# DM2080_LEFT_OV9782.net
KiCad netlist of a schematic drawn in Altium Designer
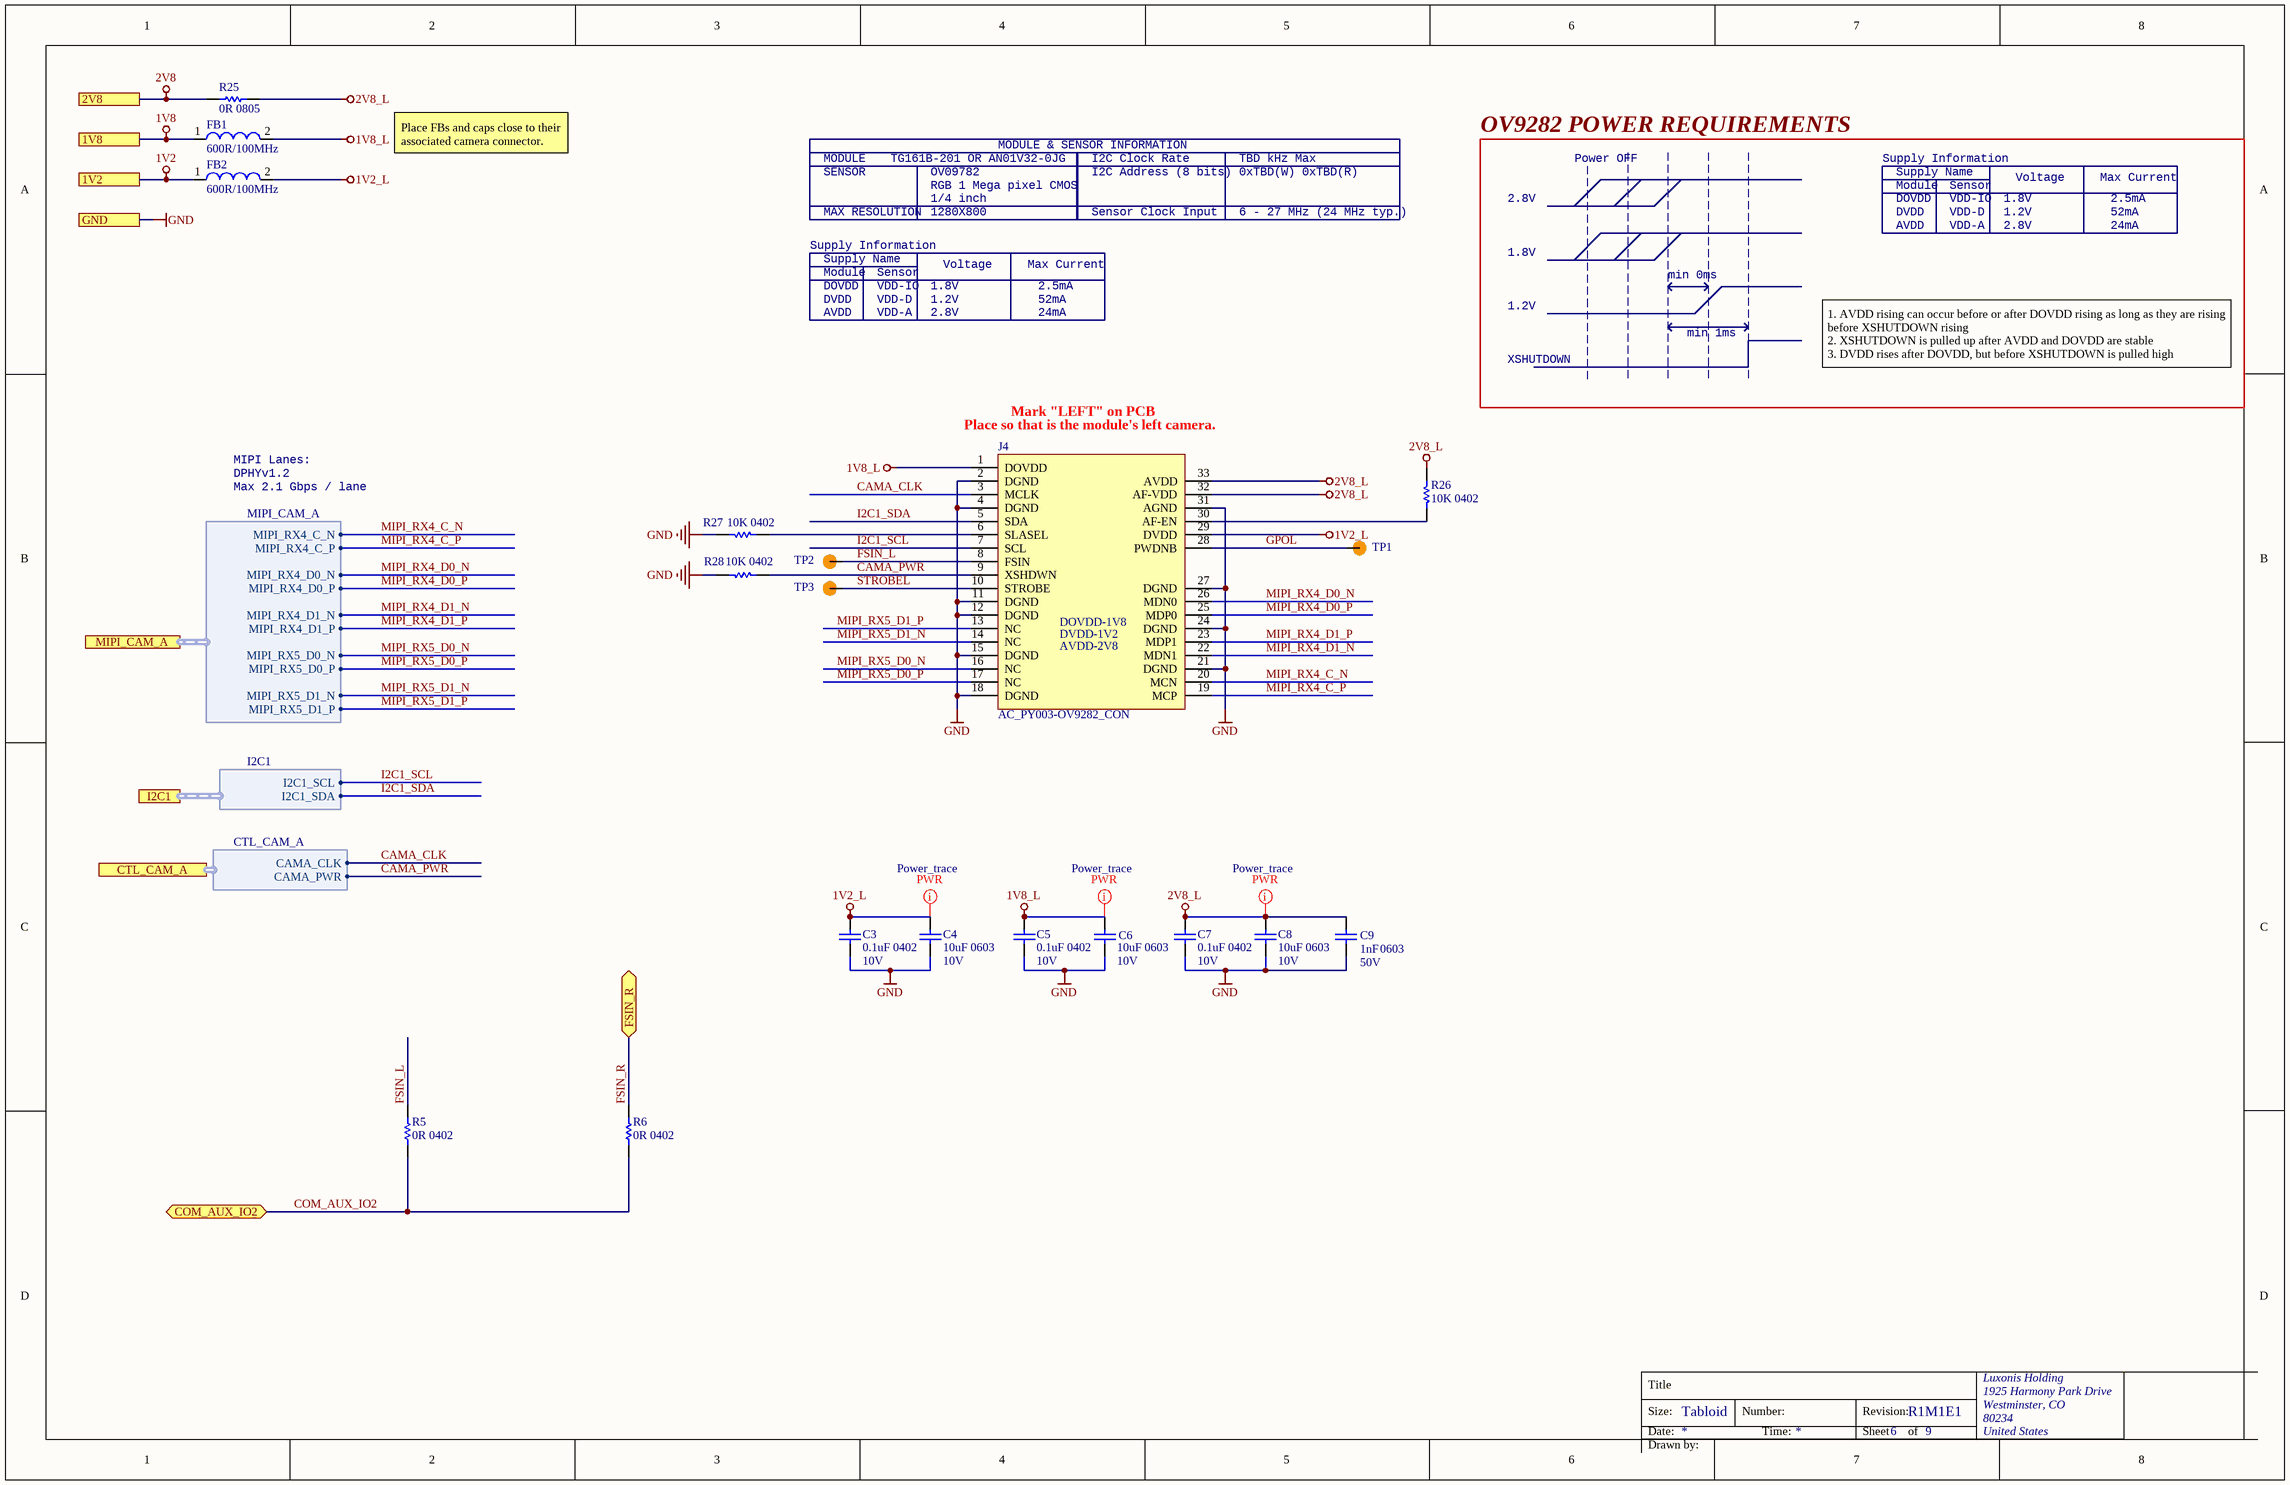
[diagram p0: DM2080_LEFT_OV9782.SchDoc]

(export (version "E")
  (design (tool "Eeschema 10.0.6"))
  (components
    (comp (ref "C3")
      (value "0.1uF 0402")
      (footprint "CAP_Altium_Vault_Generic:CAPC0402(1005)70_L")
      (description "CAP CER 0.1UF 10V X7R 0402 5%")
      (fields (field (name "TOLERANCE") "5%") (field (name "VOLTAGE RATING") "10V"))
      (libsource (lib "LuxonisMaster") (part "GRM155R71A104JA01D"))
    )
    (comp (ref "C4")
      (value "10uF 0603")
      (footprint "CAP_Altium_Vault_Generic:CAPC0603(1608)100_L")
      (description "CAP CER 10UF 10V X5R 0603 20%")
      (fields (field (name "TOLERANCE") "20%") (field (name "VOLTAGE RATING") "10V"))
      (libsource (lib "LuxonisMaster") (part "GRM188R61A106ME69D"))
    )
    (comp (ref "C5")
      (value "0.1uF 0402")
      (footprint "CAP_Altium_Vault_Generic:CAPC0402(1005)70_L")
      (description "CAP CER 0.1UF 10V X7R 0402 5%")
      (fields (field (name "TOLERANCE") "5%") (field (name "VOLTAGE RATING") "10V"))
      (libsource (lib "LuxonisMaster") (part "GRM155R71A104JA01D"))
    )
    (comp (ref "C6")
      (value "10uF 0603")
      (footprint "CAP_Altium_Vault_Generic:CAPC0603(1608)100_L")
      (description "CAP CER 10UF 10V X5R 0603 20%")
      (fields (field (name "TOLERANCE") "20%") (field (name "VOLTAGE RATING") "10V"))
      (libsource (lib "LuxonisMaster") (part "GRM188R61A106ME69D"))
    )
    (comp (ref "C7")
      (value "0.1uF 0402")
      (footprint "CAP_Altium_Vault_Generic:CAPC0402(1005)70_L")
      (description "CAP CER 0.1UF 10V X7R 0402 5%")
      (fields (field (name "TOLERANCE") "5%") (field (name "VOLTAGE RATING") "10V"))
      (libsource (lib "LuxonisMaster") (part "GRM155R71A104JA01D"))
    )
    (comp (ref "C8")
      (value "10uF 0603")
      (footprint "CAP_Altium_Vault_Generic:CAPC0603(1608)100_L")
      (description "CAP CER 10UF 10V X5R 0603 20%")
      (fields (field (name "TOLERANCE") "20%") (field (name "VOLTAGE RATING") "10V"))
      (libsource (lib "LuxonisMaster") (part "GRM188R61A106ME69D"))
    )
    (comp (ref "C9")
      (value "1nF 0603 C0G")
      (footprint "CAP_Altium_Vault_Generic:CAPC0603(1608)100_L")
      (description "CAP CER 1000PF 50V C0G/NP0 0603")
      (fields
        (field (name "MANUFACTURER") "Murata")
        (field (name "MANUFACTURER PART NUMBER") "GRM1885C1H102FA01D")
        (field (name "CASE/PACKAGE") "0603")
        (field (name "CAPACITANCE") "1nF")
        (field (name "VOLTAGE RATING") "50V")
      )
      (libsource (lib "LuxonisMaster") (part "GRM1885C1H102FA01D"))
    )
    (comp (ref "FB1")
      (value "600R/100MHz")
      (footprint "LuxonisMaster:2508056017Y2")
      (description "FERRITE BEAD, 0.1OHM, 2A, 0805, 600R/100MHz")
      (fields (field (name "TOLERANCE") "25%"))
      (libsource (lib "LuxonisMaster") (part "2508056017Y2"))
    )
    (comp (ref "FB2")
      (value "600R/100MHz")
      (footprint "LuxonisMaster:2508056017Y2")
      (description "FERRITE BEAD, 0.1OHM, 2A, 0805, 600R/100MHz")
      (fields (field (name "TOLERANCE") "25%"))
      (libsource (lib "LuxonisMaster") (part "2508056017Y2"))
    )
    (comp (ref "J4")
      (value "AC_PY003-OV9282_CON")
      (footprint "AC-PY003-OV9282")
      (description "FFC/FPC Connector, 33 Contact(s), 1 Row(s), Female, Right Angle, Surface Mount Terminal")
      (libsource (lib "Luxonis LLC") (part "AC_PY003-OV9282_CON"))
    )
    (comp (ref "R5")
      (value "0R 0402")
      (footprint "RES_Altium_Vault_Generic:RESC0402(1005)_L")
      (description "RES SMD 0 OHM JUMPER 1/16W 0402")
      (fields (field (name "TOLERANCE") "5%"))
      (libsource (lib "LuxonisMaster") (part "CRCW04020000Z0ED"))
    )
    (comp (ref "R6")
      (value "0R 0402")
      (footprint "RES_Altium_Vault_Generic:RESC0402(1005)_L")
      (description "RES SMD 0 OHM JUMPER 1/16W 0402")
      (fields (field (name "TOLERANCE") "5%"))
      (libsource (lib "LuxonisMaster") (part "CRCW04020000Z0ED"))
    )
    (comp (ref "R25")
      (value "0R 0805")
      (footprint "RESC0805(2012)_L")
      (description "RES SMD 0.0R OHM 1% 1/8W 0805")
      (libsource (lib "LuxonisMaster") (part "CRCW08050000Z0EA"))
    )
    (comp (ref "R26")
      (value "10K 0402")
      (footprint "RES_Altium_Vault_Generic:RESC0402(1005)_L")
      (fields (field (name "TOLERANCE") "1%"))
      (libsource (lib "LuxonisMaster") (part "RC0402FR-1310KL"))
    )
    (comp (ref "R27")
      (value "10K 0402")
      (footprint "RES_Altium_Vault_Generic:RESC0402(1005)_L")
      (fields (field (name "TOLERANCE") "1%"))
      (libsource (lib "LuxonisMaster") (part "RC0402FR-1310KL"))
    )
    (comp (ref "R28")
      (value "10K 0402")
      (footprint "RES_Altium_Vault_Generic:RESC0402(1005)_L")
      (fields (field (name "TOLERANCE") "1%"))
      (libsource (lib "LuxonisMaster") (part "RC0402FR-1310KL"))
    )
    (comp (ref "TP1")
      (value "TP100_200_NS")
      (footprint "LuxonisMaster:TP100_200_NS")
      (libsource (lib "LuxonisMaster") (part "TEST_POINT"))
    )
    (comp (ref "TP2")
      (value "TP100_200_NS")
      (footprint "LuxonisMaster:TP100_200_NS")
      (libsource (lib "LuxonisMaster") (part "TEST_POINT"))
    )
    (comp (ref "TP3")
      (value "TP100_200_NS")
      (footprint "LuxonisMaster:TP100_200_NS")
      (libsource (lib "LuxonisMaster") (part "TEST_POINT"))
    )
  )
  (nets
    (net (code "4") (name "/CAMA_CLK") (class "Default")
      (node (ref "J4") (pin "3") (pinfunction "MCLK_3") (pintype "passive"))
    )
    (net (code "5") (name "/CAMA_PWR") (class "Default")
      (node (ref "J4") (pin "9") (pinfunction "XSHDWN_9") (pintype "passive"))
      (node (ref "R28") (pin "1") (pinfunction "1_1") (pintype "passive"))
    )
    (net (code "6") (name "/COM_AUX_IO2") (class "Default")
      (node (ref "R5") (pin "2") (pinfunction "2_2") (pintype "passive"))
      (node (ref "R6") (pin "2") (pinfunction "2_2") (pintype "passive"))
    )
    (net (code "7") (name "/FSIN_L") (class "Default")
      (node (ref "J4") (pin "8") (pinfunction "FSIN_8") (pintype "passive"))
      (node (ref "R5") (pin "1") (pinfunction "1_1") (pintype "passive"))
      (node (ref "TP2") (pin "1") (pintype "passive"))
    )
    (net (code "8") (name "/FSIN_R") (class "Default")
      (node (ref "R6") (pin "1") (pinfunction "1_1") (pintype "passive"))
    )
    (net (code "9") (name "/GPOL") (class "Default")
      (node (ref "J4") (pin "28") (pinfunction "PWDNB_28") (pintype "passive"))
      (node (ref "TP1") (pin "1") (pintype "passive"))
    )
    (net (code "10") (name "/I2C1_SCL") (class "Default")
      (node (ref "J4") (pin "7") (pinfunction "SCL_7") (pintype "passive"))
    )
    (net (code "11") (name "/I2C1_SDA") (class "Default")
      (node (ref "J4") (pin "5") (pinfunction "SDA_5") (pintype "passive"))
    )
    (net (code "12") (name "/MIPI_RX4_C_N") (class "Default")
      (node (ref "J4") (pin "20") (pinfunction "MCN_20") (pintype "passive"))
    )
    (net (code "13") (name "/MIPI_RX4_C_P") (class "Default")
      (node (ref "J4") (pin "19") (pinfunction "MCP_19") (pintype "passive"))
    )
    (net (code "14") (name "/MIPI_RX4_D0_N") (class "Default")
      (node (ref "J4") (pin "26") (pinfunction "MDN0_26") (pintype "passive"))
    )
    (net (code "15") (name "/MIPI_RX4_D0_P") (class "Default")
      (node (ref "J4") (pin "25") (pinfunction "MDP0_25") (pintype "passive"))
    )
    (net (code "16") (name "/MIPI_RX4_D1_N") (class "Default")
      (node (ref "J4") (pin "22") (pinfunction "MDN1_22") (pintype "passive"))
    )
    (net (code "17") (name "/MIPI_RX4_D1_P") (class "Default")
      (node (ref "J4") (pin "23") (pinfunction "MDP1_23") (pintype "passive"))
    )
    (net (code "18") (name "/MIPI_RX5_D0_N") (class "Default")
      (node (ref "J4") (pin "16") (pinfunction "NC_16") (pintype "passive"))
    )
    (net (code "19") (name "/MIPI_RX5_D0_P") (class "Default")
      (node (ref "J4") (pin "17") (pinfunction "NC_17") (pintype "passive"))
    )
    (net (code "20") (name "/MIPI_RX5_D1_N") (class "Default")
      (node (ref "J4") (pin "14") (pinfunction "NC_14") (pintype "passive"))
    )
    (net (code "21") (name "/MIPI_RX5_D1_P") (class "Default")
      (node (ref "J4") (pin "13") (pinfunction "NC_13") (pintype "passive"))
    )
    (net (code "22") (name "/STROBEL") (class "Default")
      (node (ref "J4") (pin "10") (pinfunction "STROBE_10") (pintype "passive"))
      (node (ref "TP3") (pin "1") (pintype "passive"))
    )
    (net (code "26") (name "1V2") (class "Default")
      (node (ref "FB2") (pin "1") (pinfunction "1_1") (pintype "passive"))
    )
    (net (code "27") (name "1V2_L") (class "Default")
      (node (ref "C3") (pin "2") (pinfunction "2_2") (pintype "passive"))
      (node (ref "C4") (pin "2") (pinfunction "2_2") (pintype "passive"))
      (node (ref "FB2") (pin "2") (pinfunction "2_2") (pintype "passive"))
      (node (ref "J4") (pin "29") (pinfunction "DVDD_29") (pintype "passive"))
    )
    (net (code "28") (name "1V8") (class "Default")
      (node (ref "FB1") (pin "1") (pinfunction "1_1") (pintype "passive"))
    )
    (net (code "29") (name "1V8_L") (class "Default")
      (node (ref "C5") (pin "2") (pinfunction "2_2") (pintype "passive"))
      (node (ref "C6") (pin "2") (pinfunction "2_2") (pintype "passive"))
      (node (ref "FB1") (pin "2") (pinfunction "2_2") (pintype "passive"))
      (node (ref "J4") (pin "1") (pinfunction "DOVDD_1") (pintype "passive"))
    )
    (net (code "30") (name "2V8") (class "Default")
      (node (ref "R25") (pin "1") (pinfunction "1_1") (pintype "passive"))
    )
    (net (code "31") (name "2V8_L") (class "Default")
      (node (ref "C7") (pin "2") (pinfunction "2_2") (pintype "passive"))
      (node (ref "C8") (pin "2") (pinfunction "2_2") (pintype "passive"))
      (node (ref "C9") (pin "2") (pinfunction "2_2") (pintype "passive"))
      (node (ref "J4") (pin "32") (pinfunction "AF-VDD_32") (pintype "passive"))
      (node (ref "J4") (pin "33") (pinfunction "AVDD_33") (pintype "passive"))
      (node (ref "R25") (pin "2") (pinfunction "2_2") (pintype "passive"))
      (node (ref "R26") (pin "1") (pinfunction "1_1") (pintype "passive"))
    )
    (net (code "32") (name "GND") (class "Default")
      (node (ref "C3") (pin "1") (pinfunction "1_1") (pintype "passive"))
      (node (ref "C4") (pin "1") (pinfunction "1_1") (pintype "passive"))
      (node (ref "C5") (pin "1") (pinfunction "1_1") (pintype "passive"))
      (node (ref "C6") (pin "1") (pinfunction "1_1") (pintype "passive"))
      (node (ref "C7") (pin "1") (pinfunction "1_1") (pintype "passive"))
      (node (ref "C8") (pin "1") (pinfunction "1_1") (pintype "passive"))
      (node (ref "C9") (pin "1") (pinfunction "1_1") (pintype "passive"))
      (node (ref "J4") (pin "11") (pinfunction "DGND_11") (pintype "passive"))
      (node (ref "J4") (pin "12") (pinfunction "DGND_12") (pintype "passive"))
      (node (ref "J4") (pin "15") (pinfunction "DGND_15") (pintype "passive"))
      (node (ref "J4") (pin "18") (pinfunction "DGND_18") (pintype "passive"))
      (node (ref "J4") (pin "2") (pinfunction "DGND_2") (pintype "passive"))
      (node (ref "J4") (pin "21") (pinfunction "DGND_21") (pintype "passive"))
      (node (ref "J4") (pin "24") (pinfunction "DGND_24") (pintype "passive"))
      (node (ref "J4") (pin "27") (pinfunction "DGND_27") (pintype "passive"))
      (node (ref "J4") (pin "31") (pinfunction "AGND_31") (pintype "passive"))
      (node (ref "J4") (pin "4") (pinfunction "DGND_4") (pintype "passive"))
      (node (ref "R27") (pin "2") (pinfunction "2_2") (pintype "passive"))
      (node (ref "R28") (pin "2") (pinfunction "2_2") (pintype "passive"))
    )
    (net (code "33") (name "Net-(J4-AF-EN)") (class "Default")
      (node (ref "J4") (pin "30") (pinfunction "AF-EN_30") (pintype "passive"))
      (node (ref "R26") (pin "2") (pinfunction "2_2") (pintype "passive"))
    )
    (net (code "34") (name "Net-(J4-SLASEL)") (class "Default")
      (node (ref "J4") (pin "6") (pinfunction "SLASEL_6") (pintype "passive"))
      (node (ref "R27") (pin "1") (pinfunction "1_1") (pintype "passive"))
    )
  )
)
